# WalkSensor_V2_1.net
KiCad netlist of a schematic drawn in EAGLE
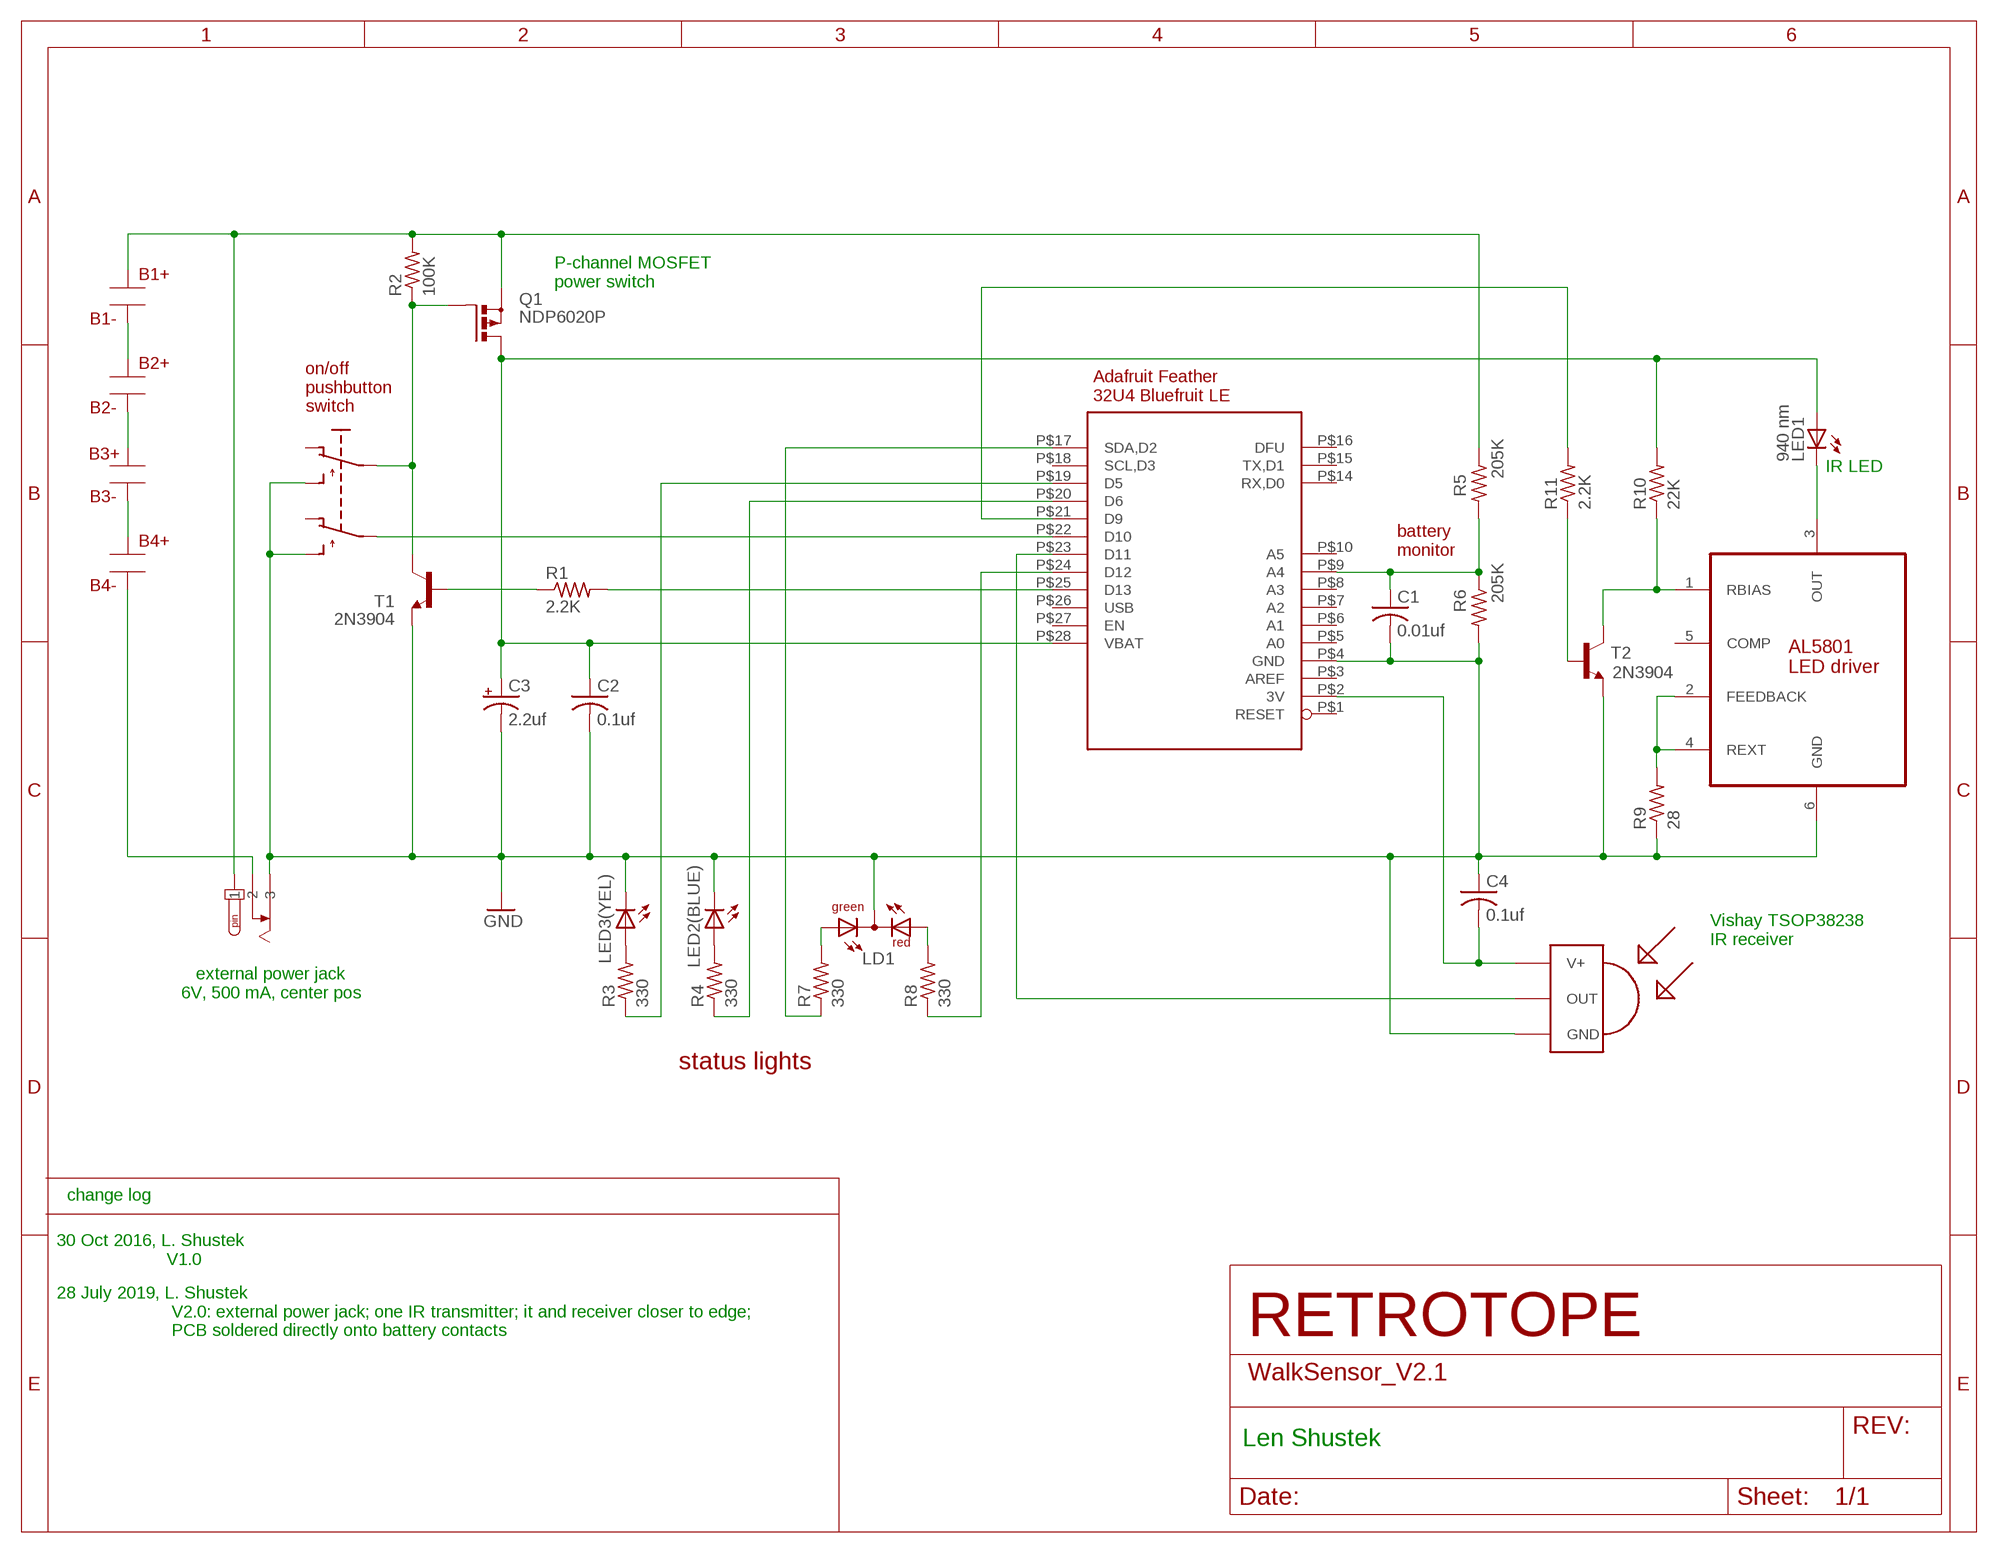
[diagram p0: schematic, sheet 1]

(export (version "E")
  (design (tool "Eeschema 10.0.6"))
  (components
    (comp (ref "B1+")
      (value "BATTERY_CONTACT")
      (footprint "eagle-import:BATTERY_CONTACT")
      (libsource (lib "eagle-import") (part "BATTERY_CONTACT"))
    )
    (comp (ref "B1-")
      (value "BATTERY_CONTACT")
      (footprint "eagle-import:BATTERY_CONTACT")
      (libsource (lib "eagle-import") (part "BATTERY_CONTACT"))
    )
    (comp (ref "B2+")
      (value "BATTERY_CONTACT")
      (footprint "eagle-import:BATTERY_CONTACT")
      (libsource (lib "eagle-import") (part "BATTERY_CONTACT"))
    )
    (comp (ref "B2-")
      (value "BATTERY_CONTACT")
      (footprint "eagle-import:BATTERY_CONTACT")
      (libsource (lib "eagle-import") (part "BATTERY_CONTACT"))
    )
    (comp (ref "B3+")
      (value "BATTERY_CONTACT")
      (footprint "eagle-import:BATTERY_CONTACT")
      (libsource (lib "eagle-import") (part "BATTERY_CONTACT"))
    )
    (comp (ref "B3-")
      (value "BATTERY_CONTACT")
      (footprint "eagle-import:BATTERY_CONTACT")
      (libsource (lib "eagle-import") (part "BATTERY_CONTACT"))
    )
    (comp (ref "B4+")
      (value "BATTERY_CONTACT")
      (footprint "eagle-import:BATTERY_CONTACT")
      (libsource (lib "eagle-import") (part "BATTERY_CONTACT"))
    )
    (comp (ref "B4-")
      (value "BATTERY_CONTACT")
      (footprint "eagle-import:BATTERY_CONTACT")
      (libsource (lib "eagle-import") (part "BATTERY_CONTACT"))
    )
    (comp (ref "C1")
      (value "0.01uf")
      (footprint "eagle-import:C025-025X050")
      (libsource (lib "eagle-import") (part "C-US025-025X050"))
    )
    (comp (ref "C2")
      (value "0.1uf")
      (footprint "eagle-import:C025-025X050")
      (libsource (lib "eagle-import") (part "C-US025-025X050"))
    )
    (comp (ref "C3")
      (value "2.2uf")
      (footprint "eagle-import:E5-6")
      (libsource (lib "eagle-import") (part "CPOL-USE5-6"))
    )
    (comp (ref "C4")
      (value "0.1uf")
      (footprint "eagle-import:C025-025X050")
      (libsource (lib "eagle-import") (part "C-US025-025X050"))
    )
    (comp (ref "J1")
      (value "DC_POWER_JACK")
      (footprint "eagle-import:DC_POWER_JACK")
      (libsource (lib "eagle-import") (part "DC_POWER_JACK"))
    )
    (comp (ref "LD1")
      (value "red/green")
      (footprint "eagle-import:DUOLED-C-5MM")
      (libsource (lib "eagle-import") (part "DUOLED-RG-C"))
    )
    (comp (ref "LED1")
      (value "940 nm")
      (footprint "eagle-import:LED3MM")
      (libsource (lib "eagle-import") (part "adafruit_LED3MM"))
    )
    (comp (ref "LED2(BLUE)")
      (value "blue")
      (footprint "eagle-import:LED5MM")
      (libsource (lib "eagle-import") (part "LED5MM"))
    )
    (comp (ref "LED3(YEL)")
      (value "yellow")
      (footprint "eagle-import:LED5MM")
      (libsource (lib "eagle-import") (part "LED5MM"))
    )
    (comp (ref "Q1")
      (value "NDP6020P")
      (footprint "eagle-import:TO220BH")
      (libsource (lib "eagle-import") (part "PMOSFET_PTO220BH"))
    )
    (comp (ref "R1")
      (value "2.2K")
      (footprint "eagle-import:0207_10")
      (libsource (lib "eagle-import") (part "R-US_0207/10"))
    )
    (comp (ref "R2")
      (value "100K")
      (footprint "eagle-import:0207_10")
      (libsource (lib "eagle-import") (part "R-US_0207/10"))
    )
    (comp (ref "R3")
      (value "330")
      (footprint "eagle-import:0207_10")
      (libsource (lib "eagle-import") (part "R-US_0207/10"))
    )
    (comp (ref "R4")
      (value "330")
      (footprint "eagle-import:0207_10")
      (libsource (lib "eagle-import") (part "R-US_0207/10"))
    )
    (comp (ref "R5")
      (value "205K")
      (footprint "eagle-import:0207_10")
      (libsource (lib "eagle-import") (part "R-US_0207/10"))
    )
    (comp (ref "R6")
      (value "205K")
      (footprint "eagle-import:0207_10")
      (libsource (lib "eagle-import") (part "R-US_0207/10"))
    )
    (comp (ref "R7")
      (value "330")
      (footprint "eagle-import:0207_10")
      (libsource (lib "eagle-import") (part "R-US_0207/10"))
    )
    (comp (ref "R8")
      (value "330")
      (footprint "eagle-import:0207_10")
      (libsource (lib "eagle-import") (part "R-US_0207/10"))
    )
    (comp (ref "R9")
      (value "28")
      (footprint "eagle-import:0207_10")
      (libsource (lib "eagle-import") (part "R-US_0207/10"))
    )
    (comp (ref "R10")
      (value "22K")
      (footprint "eagle-import:0207_10")
      (libsource (lib "eagle-import") (part "R-US_0207/10"))
    )
    (comp (ref "R11")
      (value "2.2K")
      (footprint "eagle-import:0207_10")
      (libsource (lib "eagle-import") (part "R-US_0207/10"))
    )
    (comp (ref "T1")
      (value "2N3904")
      (footprint "eagle-import:TO92-EBC")
      (libsource (lib "eagle-import") (part "NPN-TRANSISTOR"))
    )
    (comp (ref "T2")
      (value "2N3904")
      (footprint "eagle-import:TO92-EBC")
      (libsource (lib "eagle-import") (part "NPN-TRANSISTOR"))
    )
    (comp (ref "U$2")
      (value "PUSHBUTTON-DPDT")
      (footprint "eagle-import:PUSHBUTTON-DPDT")
      (libsource (lib "eagle-import") (part "PUSHBUTTON-DPDT"))
    )
    (comp (ref "U$3")
      (value "TSOP1830")
      (footprint "eagle-import:TSOP18XX")
      (libsource (lib "eagle-import") (part "TSOP1830"))
    )
    (comp (ref "U$4")
      (value "BLUEFRUIT-LE")
      (footprint "eagle-import:BLUEFRUIT-LE")
      (libsource (lib "eagle-import") (part "BLUEFRUIT-LE"))
    )
    (comp (ref "U1")
      (value "AL5801")
      (footprint "eagle-import:SOT95P280X130-6N")
      (fields (field (name "MPN") "ZXGD3005E6TA"))
      (libsource (lib "eagle-import") (part "AL5801"))
    )
  )
  (nets
    (net (code "1") (name "GND") (class "Default")
      (node (ref "C1") (pin "2") (pinfunction "2_2") (pintype "passive"))
      (node (ref "C2") (pin "2") (pinfunction "2_2") (pintype "passive"))
      (node (ref "C3") (pin "-") (pinfunction "-_-") (pintype "passive"))
      (node (ref "C4") (pin "1") (pinfunction "1_1") (pintype "passive"))
      (node (ref "J1") (pin "P$5") (pinfunction "3_P$5") (pintype "passive"))
      (node (ref "LD1") (pin "C") (pinfunction "C_C") (pintype "passive"))
      (node (ref "LED2(BLUE)") (pin "K") (pinfunction "C_K") (pintype "passive"))
      (node (ref "LED3(YEL)") (pin "K") (pinfunction "C_K") (pintype "passive"))
      (node (ref "R6") (pin "2") (pinfunction "2_2") (pintype "passive"))
      (node (ref "R9") (pin "1") (pinfunction "1_1") (pintype "passive"))
      (node (ref "T1") (pin "E") (pinfunction "E_E") (pintype "passive"))
      (node (ref "T2") (pin "E") (pinfunction "E_E") (pintype "passive"))
      (node (ref "U$2") (pin "P$1") (pinfunction "S_P$1") (pintype "passive"))
      (node (ref "U$2") (pin "P$2") (pinfunction "S1_P$2") (pintype "passive"))
      (node (ref "U$3") (pin "GND") (pinfunction "GND_GND") (pintype "bidirectional"))
      (node (ref "U$4") (pin "P$4") (pinfunction "GND_P$4") (pintype "power_in"))
      (node (ref "U1") (pin "6") (pinfunction "GND_6") (pintype "power_in"))
    )
    (net (code "2") (name "Net-(B1--PadP$1)") (class "Default")
      (node (ref "B1-") (pin "P$1") (pinfunction "P$1_P$1") (pintype "bidirectional"))
      (node (ref "B2+") (pin "P$1") (pinfunction "P$1_P$1") (pintype "bidirectional"))
    )
    (net (code "3") (name "Net-(B2--PadP$1)") (class "Default")
      (node (ref "B2-") (pin "P$1") (pinfunction "P$1_P$1") (pintype "bidirectional"))
      (node (ref "B3+") (pin "P$1") (pinfunction "P$1_P$1") (pintype "bidirectional"))
    )
    (net (code "4") (name "Net-(B3--PadP$1)") (class "Default")
      (node (ref "B3-") (pin "P$1") (pinfunction "P$1_P$1") (pintype "bidirectional"))
      (node (ref "B4+") (pin "P$1") (pinfunction "P$1_P$1") (pintype "bidirectional"))
    )
    (net (code "5") (name "Net-(J1-1)") (class "Default")
      (node (ref "B1+") (pin "P$1") (pinfunction "P$1_P$1") (pintype "bidirectional"))
      (node (ref "J1") (pin "P$1") (pinfunction "1_P$1") (pintype "passive"))
      (node (ref "Q1") (pin "S") (pinfunction "S_S") (pintype "passive"))
      (node (ref "R2") (pin "2") (pinfunction "2_2") (pintype "passive"))
      (node (ref "R5") (pin "1") (pinfunction "1_1") (pintype "passive"))
    )
    (net (code "6") (name "Net-(J1-2)") (class "Default")
      (node (ref "B4-") (pin "P$1") (pinfunction "P$1_P$1") (pintype "bidirectional"))
      (node (ref "J1") (pin "P$3") (pinfunction "2_P$3") (pintype "passive"))
    )
    (net (code "7") (name "Net-(LD1-PadAG)") (class "Default")
      (node (ref "LD1") (pin "AG") (pinfunction "AG_AG") (pintype "passive"))
      (node (ref "R7") (pin "2") (pinfunction "2_2") (pintype "passive"))
    )
    (net (code "8") (name "Net-(LD1-PadAR)") (class "Default")
      (node (ref "LD1") (pin "AR") (pinfunction "AR_AR") (pintype "passive"))
      (node (ref "R8") (pin "2") (pinfunction "2_2") (pintype "passive"))
    )
    (net (code "9") (name "Net-(LED1-C)") (class "Default")
      (node (ref "LED1") (pin "K") (pinfunction "C_K") (pintype "passive"))
      (node (ref "U1") (pin "3") (pinfunction "OUT_3") (pintype "passive"))
    )
    (net (code "10") (name "Net-(LED2(BLUE)-PadA)") (class "Default")
      (node (ref "LED2(BLUE)") (pin "A") (pinfunction "A_A") (pintype "passive"))
      (node (ref "R4") (pin "2") (pinfunction "2_2") (pintype "passive"))
    )
    (net (code "11") (name "Net-(LED3(YEL)-PadA)") (class "Default")
      (node (ref "LED3(YEL)") (pin "A") (pinfunction "A_A") (pintype "passive"))
      (node (ref "R3") (pin "2") (pinfunction "2_2") (pintype "passive"))
    )
    (net (code "12") (name "Net-(R1-Pad1)") (class "Default")
      (node (ref "R1") (pin "1") (pinfunction "1_1") (pintype "passive"))
      (node (ref "T1") (pin "B") (pinfunction "B_B") (pintype "passive"))
    )
    (net (code "13") (name "Net-(R11-Pad1)") (class "Default")
      (node (ref "R11") (pin "1") (pinfunction "1_1") (pintype "passive"))
      (node (ref "T2") (pin "B") (pinfunction "B_B") (pintype "passive"))
    )
    (net (code "14") (name "Net-(U$2-P)") (class "Default")
      (node (ref "Q1") (pin "G") (pinfunction "G_G") (pintype "passive"))
      (node (ref "R2") (pin "1") (pinfunction "1_1") (pintype "passive"))
      (node (ref "T1") (pin "C") (pinfunction "C_C") (pintype "passive"))
      (node (ref "U$2") (pin "P$5") (pinfunction "P_P$5") (pintype "passive"))
    )
    (net (code "15") (name "Net-(U$2-P1)") (class "Default")
      (node (ref "U$2") (pin "P$6") (pinfunction "P1_P$6") (pintype "passive"))
      (node (ref "U$4") (pin "P$22") (pinfunction "D10_P$22") (pintype "bidirectional"))
    )
    (net (code "16") (name "Net-(U$3-V+)") (class "Default")
      (node (ref "C4") (pin "2") (pinfunction "2_2") (pintype "passive"))
      (node (ref "U$3") (pin "VCC") (pinfunction "V+_VCC") (pintype "bidirectional"))
      (node (ref "U$4") (pin "P$2") (pinfunction "3V_P$2") (pintype "power_in"))
    )
    (net (code "17") (name "Net-(U$4-A4)") (class "Default")
      (node (ref "C1") (pin "1") (pinfunction "1_1") (pintype "passive"))
      (node (ref "R5") (pin "2") (pinfunction "2_2") (pintype "passive"))
      (node (ref "R6") (pin "1") (pinfunction "1_1") (pintype "passive"))
      (node (ref "U$4") (pin "P$9") (pinfunction "A4_P$9") (pintype "bidirectional"))
    )
    (net (code "18") (name "Net-(U$4-D5)") (class "Default")
      (node (ref "R3") (pin "1") (pinfunction "1_1") (pintype "passive"))
      (node (ref "U$4") (pin "P$19") (pinfunction "D5_P$19") (pintype "bidirectional"))
    )
    (net (code "19") (name "Net-(U$4-D6)") (class "Default")
      (node (ref "R4") (pin "1") (pinfunction "1_1") (pintype "passive"))
      (node (ref "U$4") (pin "P$20") (pinfunction "D6_P$20") (pintype "bidirectional"))
    )
    (net (code "20") (name "Net-(U$4-D9)") (class "Default")
      (node (ref "R11") (pin "2") (pinfunction "2_2") (pintype "passive"))
      (node (ref "U$4") (pin "P$21") (pinfunction "D9_P$21") (pintype "bidirectional"))
    )
    (net (code "21") (name "Net-(U$4-D11)") (class "Default")
      (node (ref "U$3") (pin "OUT") (pinfunction "OUT_OUT") (pintype "bidirectional"))
      (node (ref "U$4") (pin "P$23") (pinfunction "D11_P$23") (pintype "bidirectional"))
    )
    (net (code "22") (name "Net-(U$4-D12)") (class "Default")
      (node (ref "R8") (pin "1") (pinfunction "1_1") (pintype "passive"))
      (node (ref "U$4") (pin "P$24") (pinfunction "D12_P$24") (pintype "bidirectional"))
    )
    (net (code "23") (name "Net-(U$4-D13)") (class "Default")
      (node (ref "R1") (pin "2") (pinfunction "2_2") (pintype "passive"))
      (node (ref "U$4") (pin "P$25") (pinfunction "D13_P$25") (pintype "bidirectional"))
    )
    (net (code "24") (name "Net-(U$4-SDA,D2)") (class "Default")
      (node (ref "R7") (pin "1") (pinfunction "1_1") (pintype "passive"))
      (node (ref "U$4") (pin "P$17") (pinfunction "SDA,D2_P$17") (pintype "bidirectional"))
    )
    (net (code "25") (name "Net-(U$4-VBAT)") (class "Default")
      (node (ref "C2") (pin "1") (pinfunction "1_1") (pintype "passive"))
      (node (ref "C3") (pin "+") (pinfunction "+_+") (pintype "passive"))
      (node (ref "LED1") (pin "A") (pinfunction "A_A") (pintype "passive"))
      (node (ref "Q1") (pin "D") (pinfunction "D_D") (pintype "passive"))
      (node (ref "R10") (pin "2") (pinfunction "2_2") (pintype "passive"))
      (node (ref "U$4") (pin "P$28") (pinfunction "VBAT_P$28") (pintype "power_in"))
    )
    (net (code "26") (name "Net-(U1-FEEDBACK)") (class "Default")
      (node (ref "R9") (pin "2") (pinfunction "2_2") (pintype "passive"))
      (node (ref "U1") (pin "2") (pinfunction "FEEDBACK_2") (pintype "passive"))
      (node (ref "U1") (pin "4") (pinfunction "REXT_4") (pintype "passive"))
    )
    (net (code "27") (name "Net-(U1-RBIAS)") (class "Default")
      (node (ref "R10") (pin "1") (pinfunction "1_1") (pintype "passive"))
      (node (ref "T2") (pin "C") (pinfunction "C_C") (pintype "passive"))
      (node (ref "U1") (pin "1") (pinfunction "RBIAS_1") (pintype "passive"))
    )
    (net (code "28") (name "unconnected-(U$2-O-PadP$3)") (class "Default")
      (node (ref "U$2") (pin "P$3") (pinfunction "O_P$3") (pintype "passive"))
    )
    (net (code "29") (name "unconnected-(U$2-O1-PadP$4)") (class "Default")
      (node (ref "U$2") (pin "P$4") (pinfunction "O1_P$4") (pintype "passive"))
    )
    (net (code "30") (name "unconnected-(U$4-A0-PadP$5)") (class "Default")
      (node (ref "U$4") (pin "P$5") (pinfunction "A0_P$5") (pintype "bidirectional"))
    )
    (net (code "31") (name "unconnected-(U$4-A1-PadP$6)") (class "Default")
      (node (ref "U$4") (pin "P$6") (pinfunction "A1_P$6") (pintype "bidirectional"))
    )
    (net (code "32") (name "unconnected-(U$4-A2-PadP$7)") (class "Default")
      (node (ref "U$4") (pin "P$7") (pinfunction "A2_P$7") (pintype "bidirectional"))
    )
    (net (code "33") (name "unconnected-(U$4-A3-PadP$8)") (class "Default")
      (node (ref "U$4") (pin "P$8") (pinfunction "A3_P$8") (pintype "bidirectional"))
    )
    (net (code "34") (name "unconnected-(U$4-A5-PadP$10)") (class "Default")
      (node (ref "U$4") (pin "P$10") (pinfunction "A5_P$10") (pintype "bidirectional"))
    )
    (net (code "35") (name "unconnected-(U$4-AREF-PadP$3)") (class "Default")
      (node (ref "U$4") (pin "P$3") (pinfunction "AREF_P$3") (pintype "passive"))
    )
    (net (code "36") (name "unconnected-(U$4-DFU-PadP$16)") (class "Default")
      (node (ref "U$4") (pin "P$16") (pinfunction "DFU_P$16") (pintype "passive"))
    )
    (net (code "37") (name "unconnected-(U$4-EN-PadP$27)") (class "Default")
      (node (ref "U$4") (pin "P$27") (pinfunction "EN_P$27") (pintype "passive"))
    )
    (net (code "38") (name "unconnected-(U$4-RESET-PadP$1)") (class "Default")
      (node (ref "U$4") (pin "P$1") (pinfunction "RESET_P$1") (pintype "bidirectional"))
    )
    (net (code "39") (name "unconnected-(U$4-RX,D0-PadP$14)") (class "Default")
      (node (ref "U$4") (pin "P$14") (pinfunction "RX,D0_P$14") (pintype "bidirectional"))
    )
    (net (code "40") (name "unconnected-(U$4-SCL,D3-PadP$18)") (class "Default")
      (node (ref "U$4") (pin "P$18") (pinfunction "SCL,D3_P$18") (pintype "bidirectional"))
    )
    (net (code "41") (name "unconnected-(U$4-TX,D1-PadP$15)") (class "Default")
      (node (ref "U$4") (pin "P$15") (pinfunction "TX,D1_P$15") (pintype "bidirectional"))
    )
    (net (code "42") (name "unconnected-(U$4-USB-PadP$26)") (class "Default")
      (node (ref "U$4") (pin "P$26") (pinfunction "USB_P$26") (pintype "passive"))
    )
    (net (code "43") (name "unconnected-(U1-COMP-Pad5)") (class "Default")
      (node (ref "U1") (pin "5") (pinfunction "COMP_5") (pintype "no_connect"))
    )
  )
)
